# ProPrj_Summer_Robot_2025-05-17-22-39-37.net
KiCad netlist of a schematic drawn in EasyEDA Pro
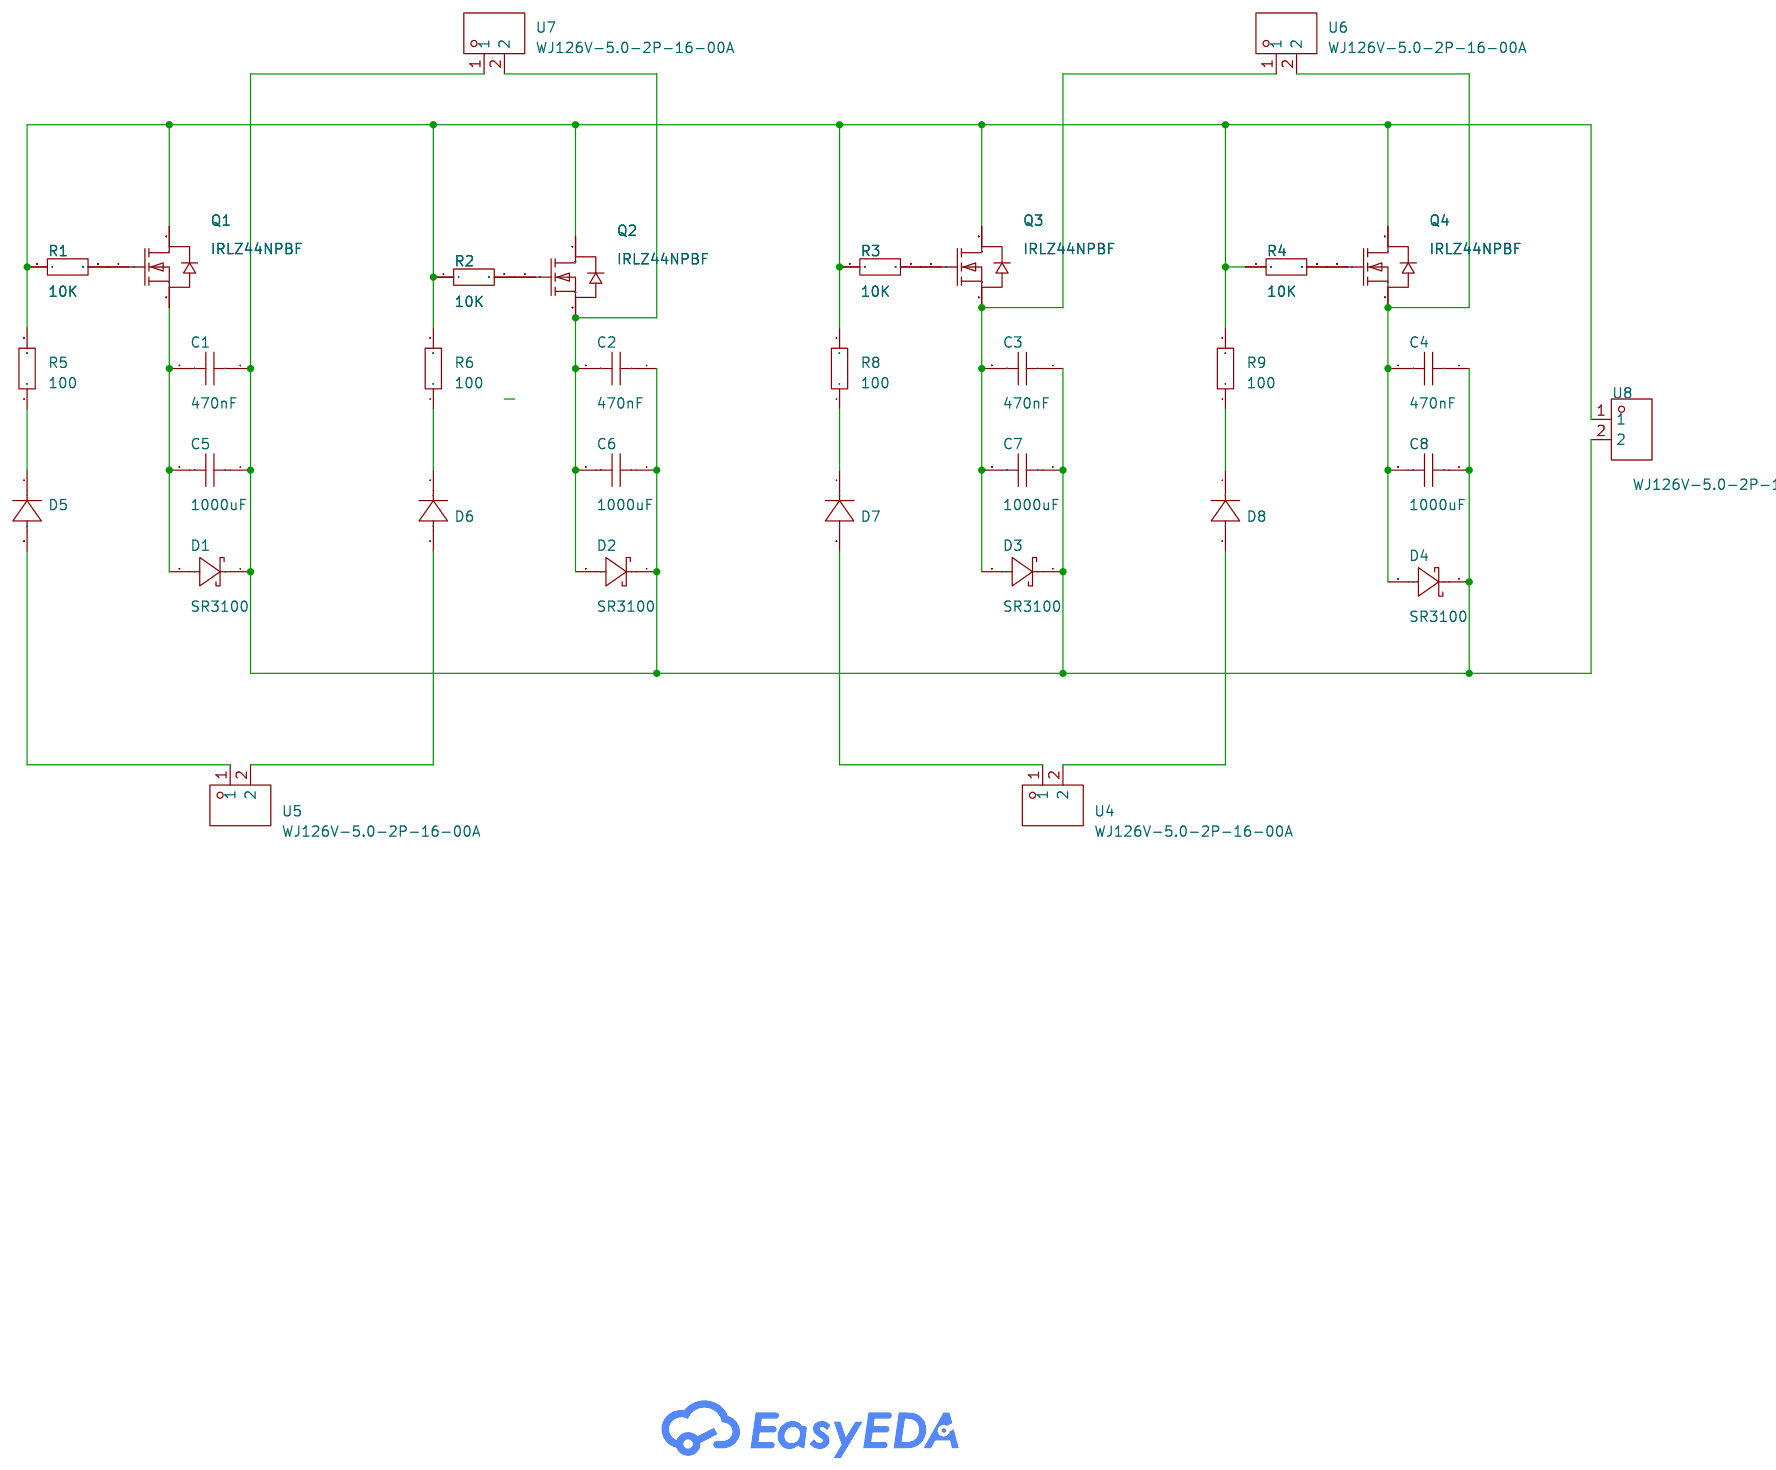
[diagram p0: schematic sheet]

(export (version "E")
  (design (tool "Eeschema 10.0.6"))
  (components
    (comp (ref "C1")
      (value "470nF")
      (footprint "easyedapro:C0603")
      (libsource (lib "easyedapro") (part "CAP"))
    )
    (comp (ref "C2")
      (value "470nF")
      (footprint "easyedapro:C0603")
      (libsource (lib "easyedapro") (part "CAP"))
    )
    (comp (ref "C3")
      (value "470nF")
      (footprint "easyedapro:C0603")
      (libsource (lib "easyedapro") (part "CAP"))
    )
    (comp (ref "C4")
      (value "470nF")
      (footprint "easyedapro:C0603")
      (libsource (lib "easyedapro") (part "CAP"))
    )
    (comp (ref "C5")
      (value "1000uF")
      (footprint "easyedapro:C0603")
      (libsource (lib "easyedapro") (part "CAP"))
    )
    (comp (ref "C6")
      (value "1000uF")
      (footprint "easyedapro:C0603")
      (libsource (lib "easyedapro") (part "CAP"))
    )
    (comp (ref "C7")
      (value "1000uF")
      (footprint "easyedapro:C0603")
      (libsource (lib "easyedapro") (part "CAP"))
    )
    (comp (ref "C8")
      (value "1000uF")
      (footprint "easyedapro:C0603")
      (libsource (lib "easyedapro") (part "CAP"))
    )
    (comp (ref "D1")
      (value "SR3100")
      (footprint "easyedapro:DO-201AD_BD5.3-L8.4-P12.50-D1.4-RD")
      (fields (field (name "Manufacturer") "YANGJIE(扬杰)"))
      (libsource (lib "easyedapro") (part "SR3100_C698900"))
    )
    (comp (ref "D2")
      (value "SR3100")
      (footprint "easyedapro:DO-201AD_BD5.3-L8.4-P12.50-D1.4-RD")
      (fields (field (name "Manufacturer") "YANGJIE(扬杰)"))
      (libsource (lib "easyedapro") (part "SR3100_C698900"))
    )
    (comp (ref "D3")
      (value "SR3100")
      (footprint "easyedapro:DO-201AD_BD5.3-L8.4-P12.50-D1.4-RD")
      (fields (field (name "Manufacturer") "YANGJIE(扬杰)"))
      (libsource (lib "easyedapro") (part "SR3100_C698900"))
    )
    (comp (ref "D4")
      (value "SR3100")
      (footprint "easyedapro:DO-201AD_BD5.3-L8.4-P12.50-D1.4-RD")
      (fields (field (name "Manufacturer") "YANGJIE(扬杰)"))
      (libsource (lib "easyedapro") (part "SR3100_C698900"))
    )
    (comp (ref "D5")
      (value "~")
      (footprint "easyedapro:DO-41_BD2.4-L4.7-P8.70-D0.9-RD")
      (libsource (lib "easyedapro") (part "D_1N4007"))
    )
    (comp (ref "D6")
      (value "~")
      (footprint "easyedapro:DO-41_BD2.4-L4.7-P8.70-D0.9-RD")
      (libsource (lib "easyedapro") (part "D_1N4007"))
    )
    (comp (ref "D7")
      (value "~")
      (footprint "easyedapro:DO-41_BD2.4-L4.7-P8.70-D0.9-RD")
      (libsource (lib "easyedapro") (part "D_1N4007"))
    )
    (comp (ref "D8")
      (value "~")
      (footprint "easyedapro:DO-41_BD2.4-L4.7-P8.70-D0.9-RD")
      (libsource (lib "easyedapro") (part "D_1N4007"))
    )
    (comp (ref "Q1")
      (value "IRLZ44NPBF")
      (footprint "easyedapro:TO-220-3_L10.0-W4.5-P2.54-T")
      (fields (field (name "Manufacturer") "Infineon(英飞凌)"))
      (libsource (lib "easyedapro") (part "IRLZ44NPBF"))
    )
    (comp (ref "Q2")
      (value "IRLZ44NPBF")
      (footprint "easyedapro:TO-220-3_L10.0-W4.5-P2.54-T")
      (fields (field (name "Manufacturer") "Infineon(英飞凌)"))
      (libsource (lib "easyedapro") (part "IRLZ44NPBF"))
    )
    (comp (ref "Q3")
      (value "IRLZ44NPBF")
      (footprint "easyedapro:TO-220-3_L10.0-W4.5-P2.54-T")
      (fields (field (name "Manufacturer") "Infineon(英飞凌)"))
      (libsource (lib "easyedapro") (part "IRLZ44NPBF"))
    )
    (comp (ref "Q4")
      (value "IRLZ44NPBF")
      (footprint "easyedapro:TO-220-3_L10.0-W4.5-P2.54-T")
      (fields (field (name "Manufacturer") "Infineon(英飞凌)"))
      (libsource (lib "easyedapro") (part "IRLZ44NPBF"))
    )
    (comp (ref "R1") (value "10K") (footprint "easyedapro:R0603") (libsource (lib "easyedapro") (part "Res")))
    (comp (ref "R2") (value "10K") (footprint "easyedapro:R0603") (libsource (lib "easyedapro") (part "Res")))
    (comp (ref "R3") (value "10K") (footprint "easyedapro:R0603") (libsource (lib "easyedapro") (part "Res")))
    (comp (ref "R4") (value "10K") (footprint "easyedapro:R0603") (libsource (lib "easyedapro") (part "Res")))
    (comp (ref "R5") (value "100") (footprint "easyedapro:R0603") (libsource (lib "easyedapro") (part "Res")))
    (comp (ref "R6") (value "100") (footprint "easyedapro:R0603") (libsource (lib "easyedapro") (part "Res")))
    (comp (ref "R8") (value "100") (footprint "easyedapro:R0603") (libsource (lib "easyedapro") (part "Res")))
    (comp (ref "R9") (value "100") (footprint "easyedapro:R0603") (libsource (lib "easyedapro") (part "Res")))
    (comp (ref "U4")
      (value "WJ126V-5.0-2P-16-00A")
      (footprint "easyedapro:CONN-TH_WJ126V-5.0-2P")
      (fields (field (name "Manufacturer") "KANGNEX(康奈克斯电气)"))
      (libsource (lib "easyedapro") (part "WJ126V-5.0-2P-16-00A"))
    )
    (comp (ref "U5")
      (value "WJ126V-5.0-2P-16-00A")
      (footprint "easyedapro:CONN-TH_WJ126V-5.0-2P")
      (fields (field (name "Manufacturer") "KANGNEX(康奈克斯电气)"))
      (libsource (lib "easyedapro") (part "WJ126V-5.0-2P-16-00A"))
    )
    (comp (ref "U6")
      (value "WJ126V-5.0-2P-16-00A")
      (footprint "easyedapro:CONN-TH_WJ126V-5.0-2P")
      (fields (field (name "Manufacturer") "KANGNEX(康奈克斯电气)"))
      (libsource (lib "easyedapro") (part "WJ126V-5.0-2P-16-00A"))
    )
    (comp (ref "U7")
      (value "WJ126V-5.0-2P-16-00A")
      (footprint "easyedapro:CONN-TH_WJ126V-5.0-2P")
      (fields (field (name "Manufacturer") "KANGNEX(康奈克斯电气)"))
      (libsource (lib "easyedapro") (part "WJ126V-5.0-2P-16-00A"))
    )
    (comp (ref "U8")
      (value "WJ126V-5.0-2P-16-00A")
      (footprint "easyedapro:CONN-TH_WJ126V-5.0-2P")
      (fields (field (name "Manufacturer") "KANGNEX(康奈克斯电气)"))
      (libsource (lib "easyedapro") (part "WJ126V-5.0-2P-16-00A"))
    )
  )
  (nets
    (net (code "1") (name "Net-(D1-A)") (class "Default")
      (node (ref "C1") (pin "2") (pinfunction "2_2") (pintype "input"))
      (node (ref "C5") (pin "2") (pinfunction "2_2") (pintype "input"))
      (node (ref "D1") (pin "2") (pinfunction "A_2") (pintype "unspecified"))
      (node (ref "Q1") (pin "3") (pinfunction "S_3") (pintype "unspecified"))
    )
    (net (code "2") (name "Net-(D1-K)") (class "Default")
      (node (ref "C1") (pin "1") (pinfunction "1_1") (pintype "input"))
      (node (ref "C2") (pin "1") (pinfunction "1_1") (pintype "input"))
      (node (ref "C3") (pin "1") (pinfunction "1_1") (pintype "input"))
      (node (ref "C4") (pin "1") (pinfunction "1_1") (pintype "input"))
      (node (ref "C5") (pin "1") (pinfunction "1_1") (pintype "input"))
      (node (ref "C6") (pin "1") (pinfunction "1_1") (pintype "input"))
      (node (ref "C7") (pin "1") (pinfunction "1_1") (pintype "input"))
      (node (ref "C8") (pin "1") (pinfunction "1_1") (pintype "input"))
      (node (ref "D1") (pin "1") (pinfunction "K_1") (pintype "unspecified"))
      (node (ref "D2") (pin "1") (pinfunction "K_1") (pintype "unspecified"))
      (node (ref "D3") (pin "1") (pinfunction "K_1") (pintype "unspecified"))
      (node (ref "D4") (pin "1") (pinfunction "K_1") (pintype "unspecified"))
      (node (ref "U7") (pin "1") (pinfunction "1_1") (pintype "unspecified"))
      (node (ref "U8") (pin "2") (pinfunction "2_2") (pintype "unspecified"))
    )
    (net (code "3") (name "Net-(D2-A)") (class "Default")
      (node (ref "C2") (pin "2") (pinfunction "2_2") (pintype "input"))
      (node (ref "C6") (pin "2") (pinfunction "2_2") (pintype "input"))
      (node (ref "D2") (pin "2") (pinfunction "A_2") (pintype "unspecified"))
      (node (ref "Q2") (pin "3") (pinfunction "S_3") (pintype "unspecified"))
      (node (ref "U7") (pin "2") (pinfunction "2_2") (pintype "unspecified"))
    )
    (net (code "4") (name "Net-(D3-A)") (class "Default")
      (node (ref "C3") (pin "2") (pinfunction "2_2") (pintype "input"))
      (node (ref "C7") (pin "2") (pinfunction "2_2") (pintype "input"))
      (node (ref "D3") (pin "2") (pinfunction "A_2") (pintype "unspecified"))
      (node (ref "Q3") (pin "3") (pinfunction "S_3") (pintype "unspecified"))
      (node (ref "U6") (pin "1") (pinfunction "1_1") (pintype "unspecified"))
    )
    (net (code "5") (name "Net-(D4-A)") (class "Default")
      (node (ref "C4") (pin "2") (pinfunction "2_2") (pintype "input"))
      (node (ref "C8") (pin "2") (pinfunction "2_2") (pintype "input"))
      (node (ref "D4") (pin "2") (pinfunction "A_2") (pintype "unspecified"))
      (node (ref "Q4") (pin "3") (pinfunction "S_3") (pintype "unspecified"))
      (node (ref "U6") (pin "2") (pinfunction "2_2") (pintype "unspecified"))
    )
    (net (code "6") (name "Net-(D5-A)") (class "Default")
      (node (ref "D5") (pin "2") (pinfunction "A_2") (pintype "input"))
      (node (ref "U5") (pin "1") (pinfunction "1_1") (pintype "unspecified"))
    )
    (net (code "7") (name "Net-(D5-K)") (class "Default")
      (node (ref "D5") (pin "1") (pinfunction "K_1") (pintype "input"))
      (node (ref "R5") (pin "1") (pinfunction "1_1") (pintype "input"))
    )
    (net (code "8") (name "Net-(D6-A)") (class "Default")
      (node (ref "D6") (pin "2") (pinfunction "A_2") (pintype "input"))
      (node (ref "U5") (pin "2") (pinfunction "2_2") (pintype "unspecified"))
    )
    (net (code "9") (name "Net-(D6-K)") (class "Default")
      (node (ref "D6") (pin "1") (pinfunction "K_1") (pintype "input"))
      (node (ref "R6") (pin "1") (pinfunction "1_1") (pintype "input"))
    )
    (net (code "10") (name "Net-(D7-A)") (class "Default")
      (node (ref "D7") (pin "2") (pinfunction "A_2") (pintype "input"))
      (node (ref "U4") (pin "1") (pinfunction "1_1") (pintype "unspecified"))
    )
    (net (code "11") (name "Net-(D7-K)") (class "Default")
      (node (ref "D7") (pin "1") (pinfunction "K_1") (pintype "input"))
      (node (ref "R8") (pin "1") (pinfunction "1_1") (pintype "input"))
    )
    (net (code "12") (name "Net-(D8-A)") (class "Default")
      (node (ref "D8") (pin "2") (pinfunction "A_2") (pintype "input"))
      (node (ref "U4") (pin "2") (pinfunction "2_2") (pintype "unspecified"))
    )
    (net (code "13") (name "Net-(D8-K)") (class "Default")
      (node (ref "D8") (pin "1") (pinfunction "K_1") (pintype "input"))
      (node (ref "R9") (pin "1") (pinfunction "1_1") (pintype "input"))
    )
    (net (code "14") (name "Net-(Q1-D)") (class "Default")
      (node (ref "Q1") (pin "2") (pinfunction "D_2") (pintype "unspecified"))
      (node (ref "Q2") (pin "2") (pinfunction "D_2") (pintype "unspecified"))
      (node (ref "Q3") (pin "2") (pinfunction "D_2") (pintype "unspecified"))
      (node (ref "Q4") (pin "2") (pinfunction "D_2") (pintype "unspecified"))
      (node (ref "R1") (pin "1") (pinfunction "1_1") (pintype "input"))
      (node (ref "R2") (pin "1") (pinfunction "1_1") (pintype "input"))
      (node (ref "R3") (pin "1") (pinfunction "1_1") (pintype "input"))
      (node (ref "R4") (pin "1") (pinfunction "1_1") (pintype "input"))
      (node (ref "R5") (pin "2") (pinfunction "2_2") (pintype "input"))
      (node (ref "R6") (pin "2") (pinfunction "2_2") (pintype "input"))
      (node (ref "R8") (pin "2") (pinfunction "2_2") (pintype "input"))
      (node (ref "R9") (pin "2") (pinfunction "2_2") (pintype "input"))
      (node (ref "U8") (pin "1") (pinfunction "1_1") (pintype "unspecified"))
    )
    (net (code "15") (name "Net-(Q1-G)") (class "Default")
      (node (ref "Q1") (pin "1") (pinfunction "G_1") (pintype "unspecified"))
      (node (ref "R1") (pin "2") (pinfunction "2_2") (pintype "input"))
    )
    (net (code "16") (name "Net-(Q2-G)") (class "Default")
      (node (ref "Q2") (pin "1") (pinfunction "G_1") (pintype "unspecified"))
      (node (ref "R2") (pin "2") (pinfunction "2_2") (pintype "input"))
    )
    (net (code "17") (name "Net-(Q3-G)") (class "Default")
      (node (ref "Q3") (pin "1") (pinfunction "G_1") (pintype "unspecified"))
      (node (ref "R3") (pin "2") (pinfunction "2_2") (pintype "input"))
    )
    (net (code "18") (name "Net-(Q4-G)") (class "Default")
      (node (ref "Q4") (pin "1") (pinfunction "G_1") (pintype "unspecified"))
      (node (ref "R4") (pin "2") (pinfunction "2_2") (pintype "input"))
    )
  )
)
